# mipi_dsi.net
KiCad netlist of a schematic drawn in Altium Designer
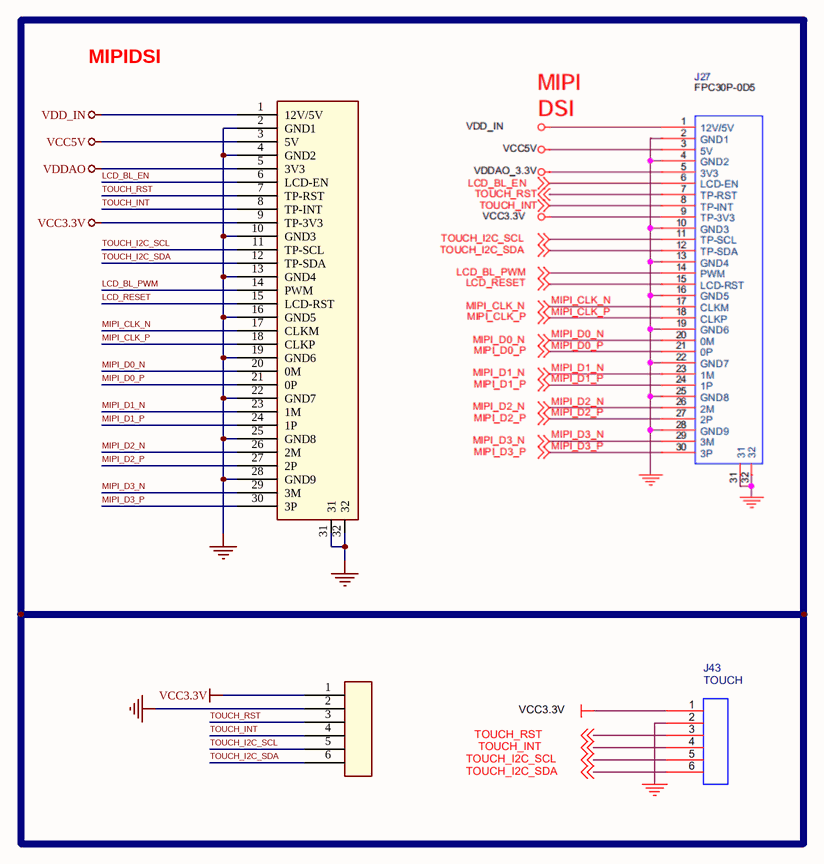
[diagram p0: mipi_dsi.SchDoc]

(export (version "E")
  (design (tool "Eeschema 10.0.6"))
  (components
    (comp (ref "J5") (value "~") (libsource (lib "*") (part "FPC30_0")))
    (comp (ref "J6") (value "~") (libsource (lib "*") (part "CON6")))
  )
  (nets
    (net (code "1") (name "/LCD_BL_EN") (class "Default")
      (node (ref "J5") (pin "6") (pinfunction "LCD-EN_6") (pintype "passive"))
    )
    (net (code "2") (name "/LCD_BL_PWM") (class "Default")
      (node (ref "J5") (pin "14") (pinfunction "PWM_14") (pintype "passive"))
    )
    (net (code "3") (name "/LCD_RESET") (class "Default")
      (node (ref "J5") (pin "15") (pinfunction "LCD-RST_15") (pintype "passive"))
    )
    (net (code "4") (name "/MIPI_CLK_N") (class "Default")
      (node (ref "J5") (pin "17") (pinfunction "CLKM_17") (pintype "passive"))
    )
    (net (code "5") (name "/MIPI_CLK_P") (class "Default")
      (node (ref "J5") (pin "18") (pinfunction "CLKP_18") (pintype "passive"))
    )
    (net (code "6") (name "/MIPI_D0_N") (class "Default")
      (node (ref "J5") (pin "20") (pinfunction "0M_20") (pintype "passive"))
    )
    (net (code "7") (name "/MIPI_D0_P") (class "Default")
      (node (ref "J5") (pin "21") (pinfunction "0P_21") (pintype "passive"))
    )
    (net (code "8") (name "/MIPI_D1_N") (class "Default")
      (node (ref "J5") (pin "23") (pinfunction "1M_23") (pintype "passive"))
    )
    (net (code "9") (name "/MIPI_D1_P") (class "Default")
      (node (ref "J5") (pin "24") (pinfunction "1P_24") (pintype "passive"))
    )
    (net (code "10") (name "/MIPI_D2_N") (class "Default")
      (node (ref "J5") (pin "26") (pinfunction "2M_26") (pintype "passive"))
    )
    (net (code "11") (name "/MIPI_D2_P") (class "Default")
      (node (ref "J5") (pin "27") (pinfunction "2P_27") (pintype "passive"))
    )
    (net (code "12") (name "/MIPI_D3_N") (class "Default")
      (node (ref "J5") (pin "29") (pinfunction "3M_29") (pintype "passive"))
    )
    (net (code "13") (name "/MIPI_D3_P") (class "Default")
      (node (ref "J5") (pin "30") (pinfunction "3P_30") (pintype "passive"))
    )
    (net (code "14") (name "/TOUCH_I2C_SCL") (class "Default")
      (node (ref "J5") (pin "11") (pinfunction "TP-SCL_11") (pintype "passive"))
      (node (ref "J6") (pin "5") (pinfunction "5_5") (pintype "passive"))
    )
    (net (code "15") (name "/TOUCH_I2C_SDA") (class "Default")
      (node (ref "J5") (pin "12") (pinfunction "TP-SDA_12") (pintype "passive"))
      (node (ref "J6") (pin "6") (pinfunction "6_6") (pintype "passive"))
    )
    (net (code "16") (name "/TOUCH_INT") (class "Default")
      (node (ref "J5") (pin "8") (pinfunction "TP-INT_8") (pintype "passive"))
      (node (ref "J6") (pin "4") (pinfunction "4_4") (pintype "passive"))
    )
    (net (code "17") (name "/TOUCH_RST") (class "Default")
      (node (ref "J5") (pin "7") (pinfunction "TP-RST_7") (pintype "passive"))
      (node (ref "J6") (pin "3") (pinfunction "3_3") (pintype "passive"))
    )
    (net (code "18") (name "<NO NET>") (class "Default")
      (node (ref "J5") (pin "10") (pinfunction "GND3_10") (pintype "passive"))
      (node (ref "J5") (pin "13") (pinfunction "GND4_13") (pintype "passive"))
      (node (ref "J5") (pin "16") (pinfunction "GND5_16") (pintype "passive"))
      (node (ref "J5") (pin "19") (pinfunction "GND6_19") (pintype "passive"))
      (node (ref "J5") (pin "2") (pinfunction "GND1_2") (pintype "passive"))
      (node (ref "J5") (pin "22") (pinfunction "GND7_22") (pintype "passive"))
      (node (ref "J5") (pin "25") (pinfunction "GND8_25") (pintype "passive"))
      (node (ref "J5") (pin "28") (pinfunction "GND9_28") (pintype "passive"))
      (node (ref "J5") (pin "31") (pinfunction "31_31") (pintype "passive"))
      (node (ref "J5") (pin "32") (pinfunction "32_32") (pintype "passive"))
      (node (ref "J5") (pin "4") (pinfunction "GND2_4") (pintype "passive"))
      (node (ref "J6") (pin "2") (pinfunction "2_2") (pintype "passive"))
    )
    (net (code "19") (name "VCC3.3V") (class "Default")
      (node (ref "J5") (pin "9") (pinfunction "TP-3V3_9") (pintype "passive"))
      (node (ref "J6") (pin "1") (pinfunction "1_1") (pintype "passive"))
    )
    (net (code "20") (name "VCC5V") (class "Default")
      (node (ref "J5") (pin "3") (pinfunction "5V_3") (pintype "passive"))
    )
    (net (code "21") (name "VDDAO") (class "Default")
      (node (ref "J5") (pin "5") (pinfunction "3V3_5") (pintype "passive"))
    )
    (net (code "22") (name "VDD_IN") (class "Default")
      (node (ref "J5") (pin "1") (pinfunction "12V/5V_1") (pintype "passive"))
    )
  )
)
